# Super_Cap_Sch.net
KiCad netlist of a schematic drawn in Altium Designer
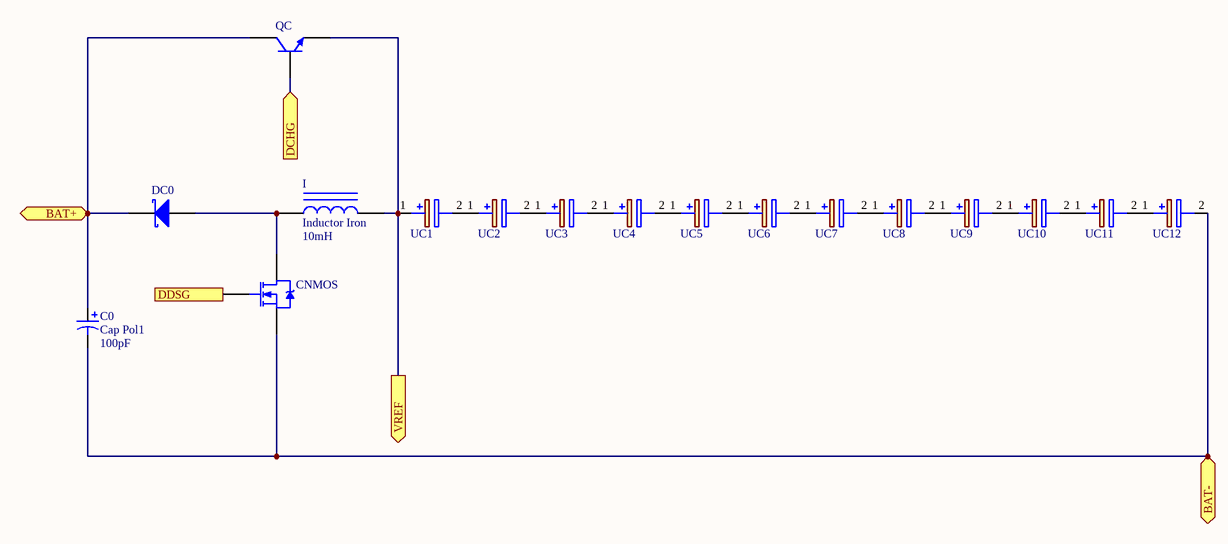
[diagram p0: Super_Cap_Sch.SchDoc]

(export (version "E")
  (design (tool "Eeschema 10.0.6"))
  (components
    (comp (ref "C0")
      (value "Cap Pol1")
      (footprint "RB7.6-15")
      (description "Polarized Capacitor (Radial)")
      (fields (field (name "ALTIUM_VALUE") "100pF") (field (name "PUBLISHER") "Altium Limited"))
      (libsource (lib "Miscellaneous Devices") (part "Cap Pol1"))
    )
    (comp (ref "CNMOS")
      (value "NMOS-2")
      (footprint "TO-220AB")
      (description "N-Channel Power MOSFET")
      (fields (field (name "PUBLISHER") "Altium Limited"))
      (libsource (lib "Miscellaneous Devices") (part "NMOS-2"))
    )
    (comp (ref "DC0")
      (value "Diode 10TQ035")
      (footprint "TO-220AC")
      (description "Schottky Rectifier")
      (fields (field (name "PUBLISHER") "Altium Limited"))
      (libsource (lib "Miscellaneous Devices") (part "Diode 10TQ035"))
    )
    (comp (ref "I")
      (value "Inductor Iron")
      (footprint "AXIAL-0.9")
      (description "Magnetic-Core Inductor")
      (fields (field (name "ALTIUM_VALUE") "10mH") (field (name "PUBLISHER") "Altium Limited"))
      (libsource (lib "Miscellaneous Devices") (part "Inductor Iron"))
    )
    (comp (ref "QC")
      (value "NPN")
      (footprint "TO-226-AA")
      (description "NPN Bipolar Transistor")
      (fields (field (name "PUBLISHER") "Altium Limited"))
      (libsource (lib "Miscellaneous Devices") (part "NPN"))
    )
    (comp (ref "UC1")
      (value "MAL223051014E3")
      (footprint "Comp_PCB:CAPPRD500W60D1300H2200")
      (description "Capacitor Polarised")
      (fields (field (name "MOUSER PART NUMBER") "594-MAL223051014E3"))
      (libsource (lib "Comp_Schm") (part "MAL223051014E3"))
    )
    (comp (ref "UC2")
      (value "MAL223051014E3")
      (footprint "Comp_PCB:CAPPRD500W60D1300H2200")
      (description "Capacitor Polarised")
      (fields (field (name "MOUSER PART NUMBER") "594-MAL223051014E3"))
      (libsource (lib "Comp_Schm") (part "MAL223051014E3"))
    )
    (comp (ref "UC3")
      (value "MAL223051014E3")
      (footprint "Comp_PCB:CAPPRD500W60D1300H2200")
      (description "Capacitor Polarised")
      (fields (field (name "MOUSER PART NUMBER") "594-MAL223051014E3"))
      (libsource (lib "Comp_Schm") (part "MAL223051014E3"))
    )
    (comp (ref "UC4")
      (value "MAL223051014E3")
      (footprint "Comp_PCB:CAPPRD500W60D1300H2200")
      (description "Capacitor Polarised")
      (fields (field (name "MOUSER PART NUMBER") "594-MAL223051014E3"))
      (libsource (lib "Comp_Schm") (part "MAL223051014E3"))
    )
    (comp (ref "UC5")
      (value "MAL223051014E3")
      (footprint "Comp_PCB:CAPPRD500W60D1300H2200")
      (description "Capacitor Polarised")
      (fields (field (name "MOUSER PART NUMBER") "594-MAL223051014E3"))
      (libsource (lib "Comp_Schm") (part "MAL223051014E3"))
    )
    (comp (ref "UC6")
      (value "MAL223051014E3")
      (footprint "Comp_PCB:CAPPRD500W60D1300H2200")
      (description "Capacitor Polarised")
      (fields (field (name "MOUSER PART NUMBER") "594-MAL223051014E3"))
      (libsource (lib "Comp_Schm") (part "MAL223051014E3"))
    )
    (comp (ref "UC7")
      (value "MAL223051014E3")
      (footprint "Comp_PCB:CAPPRD500W60D1300H2200")
      (description "Capacitor Polarised")
      (fields (field (name "MOUSER PART NUMBER") "594-MAL223051014E3"))
      (libsource (lib "Comp_Schm") (part "MAL223051014E3"))
    )
    (comp (ref "UC8")
      (value "MAL223051014E3")
      (footprint "Comp_PCB:CAPPRD500W60D1300H2200")
      (description "Capacitor Polarised")
      (fields (field (name "MOUSER PART NUMBER") "594-MAL223051014E3"))
      (libsource (lib "Comp_Schm") (part "MAL223051014E3"))
    )
    (comp (ref "UC9")
      (value "MAL223051014E3")
      (footprint "Comp_PCB:CAPPRD500W60D1300H2200")
      (description "Capacitor Polarised")
      (fields (field (name "MOUSER PART NUMBER") "594-MAL223051014E3"))
      (libsource (lib "Comp_Schm") (part "MAL223051014E3"))
    )
    (comp (ref "UC10")
      (value "MAL223051014E3")
      (footprint "Comp_PCB:CAPPRD500W60D1300H2200")
      (description "Capacitor Polarised")
      (fields (field (name "MOUSER PART NUMBER") "594-MAL223051014E3"))
      (libsource (lib "Comp_Schm") (part "MAL223051014E3"))
    )
    (comp (ref "UC11")
      (value "MAL223051014E3")
      (footprint "Comp_PCB:CAPPRD500W60D1300H2200")
      (description "Capacitor Polarised")
      (fields (field (name "MOUSER PART NUMBER") "594-MAL223051014E3"))
      (libsource (lib "Comp_Schm") (part "MAL223051014E3"))
    )
    (comp (ref "UC12")
      (value "MAL223051014E3")
      (footprint "Comp_PCB:CAPPRD500W60D1300H2200")
      (description "Capacitor Polarised")
      (fields (field (name "MOUSER PART NUMBER") "594-MAL223051014E3"))
      (libsource (lib "Comp_Schm") (part "MAL223051014E3"))
    )
  )
  (nets
    (net (code "1") (name "/BAT+") (class "Default")
      (node (ref "C0") (pin "1") (pinfunction "1_1") (pintype "passive"))
      (node (ref "DC0") (pin "1") (pinfunction "K_1") (pintype "passive"))
      (node (ref "QC") (pin "1") (pinfunction "C_1") (pintype "passive"))
    )
    (net (code "2") (name "/BAT-") (class "Default")
      (node (ref "C0") (pin "2") (pinfunction "2_2") (pintype "passive"))
      (node (ref "CNMOS") (pin "3") (pinfunction "S_3") (pintype "passive"))
      (node (ref "UC12") (pin "2") (pinfunction "-_2") (pintype "passive"))
    )
    (net (code "3") (name "/DCHG") (class "Default")
      (node (ref "QC") (pin "2") (pinfunction "B_2") (pintype "passive"))
    )
    (net (code "4") (name "/DDSG") (class "Default")
      (node (ref "CNMOS") (pin "1") (pinfunction "G_1") (pintype "passive"))
    )
    (net (code "5") (name "/VREF") (class "Default")
      (node (ref "I") (pin "2") (pinfunction "2_2") (pintype "passive"))
      (node (ref "QC") (pin "3") (pinfunction "E_3") (pintype "passive"))
      (node (ref "UC1") (pin "1") (pinfunction "+_1") (pintype "passive"))
    )
    (net (code "6") (name "Net-(CNMOS-D)") (class "Default")
      (node (ref "CNMOS") (pin "2") (pinfunction "D_2") (pintype "passive"))
      (node (ref "DC0") (pin "3") (pinfunction "A_3") (pintype "passive"))
      (node (ref "I") (pin "1") (pinfunction "1_1") (pintype "passive"))
    )
    (net (code "7") (name "Net-(UC1--)") (class "Default")
      (node (ref "UC1") (pin "2") (pinfunction "-_2") (pintype "passive"))
      (node (ref "UC2") (pin "1") (pinfunction "+_1") (pintype "passive"))
    )
    (net (code "8") (name "Net-(UC2--)") (class "Default")
      (node (ref "UC2") (pin "2") (pinfunction "-_2") (pintype "passive"))
      (node (ref "UC3") (pin "1") (pinfunction "+_1") (pintype "passive"))
    )
    (net (code "9") (name "Net-(UC3--)") (class "Default")
      (node (ref "UC3") (pin "2") (pinfunction "-_2") (pintype "passive"))
      (node (ref "UC4") (pin "1") (pinfunction "+_1") (pintype "passive"))
    )
    (net (code "10") (name "Net-(UC4--)") (class "Default")
      (node (ref "UC4") (pin "2") (pinfunction "-_2") (pintype "passive"))
      (node (ref "UC5") (pin "1") (pinfunction "+_1") (pintype "passive"))
    )
    (net (code "11") (name "Net-(UC5--)") (class "Default")
      (node (ref "UC5") (pin "2") (pinfunction "-_2") (pintype "passive"))
      (node (ref "UC6") (pin "1") (pinfunction "+_1") (pintype "passive"))
    )
    (net (code "12") (name "Net-(UC6--)") (class "Default")
      (node (ref "UC6") (pin "2") (pinfunction "-_2") (pintype "passive"))
      (node (ref "UC7") (pin "1") (pinfunction "+_1") (pintype "passive"))
    )
    (net (code "13") (name "Net-(UC7--)") (class "Default")
      (node (ref "UC7") (pin "2") (pinfunction "-_2") (pintype "passive"))
      (node (ref "UC8") (pin "1") (pinfunction "+_1") (pintype "passive"))
    )
    (net (code "14") (name "Net-(UC8--)") (class "Default")
      (node (ref "UC8") (pin "2") (pinfunction "-_2") (pintype "passive"))
      (node (ref "UC9") (pin "1") (pinfunction "+_1") (pintype "passive"))
    )
    (net (code "15") (name "Net-(UC10-+)") (class "Default")
      (node (ref "UC10") (pin "1") (pinfunction "+_1") (pintype "passive"))
      (node (ref "UC9") (pin "2") (pinfunction "-_2") (pintype "passive"))
    )
    (net (code "16") (name "Net-(UC10--)") (class "Default")
      (node (ref "UC10") (pin "2") (pinfunction "-_2") (pintype "passive"))
      (node (ref "UC11") (pin "1") (pinfunction "+_1") (pintype "passive"))
    )
    (net (code "17") (name "Net-(UC11--)") (class "Default")
      (node (ref "UC11") (pin "2") (pinfunction "-_2") (pintype "passive"))
      (node (ref "UC12") (pin "1") (pinfunction "+_1") (pintype "passive"))
    )
  )
)
